# midicontrol_v4.net
KiCad netlist of a schematic drawn in EAGLE
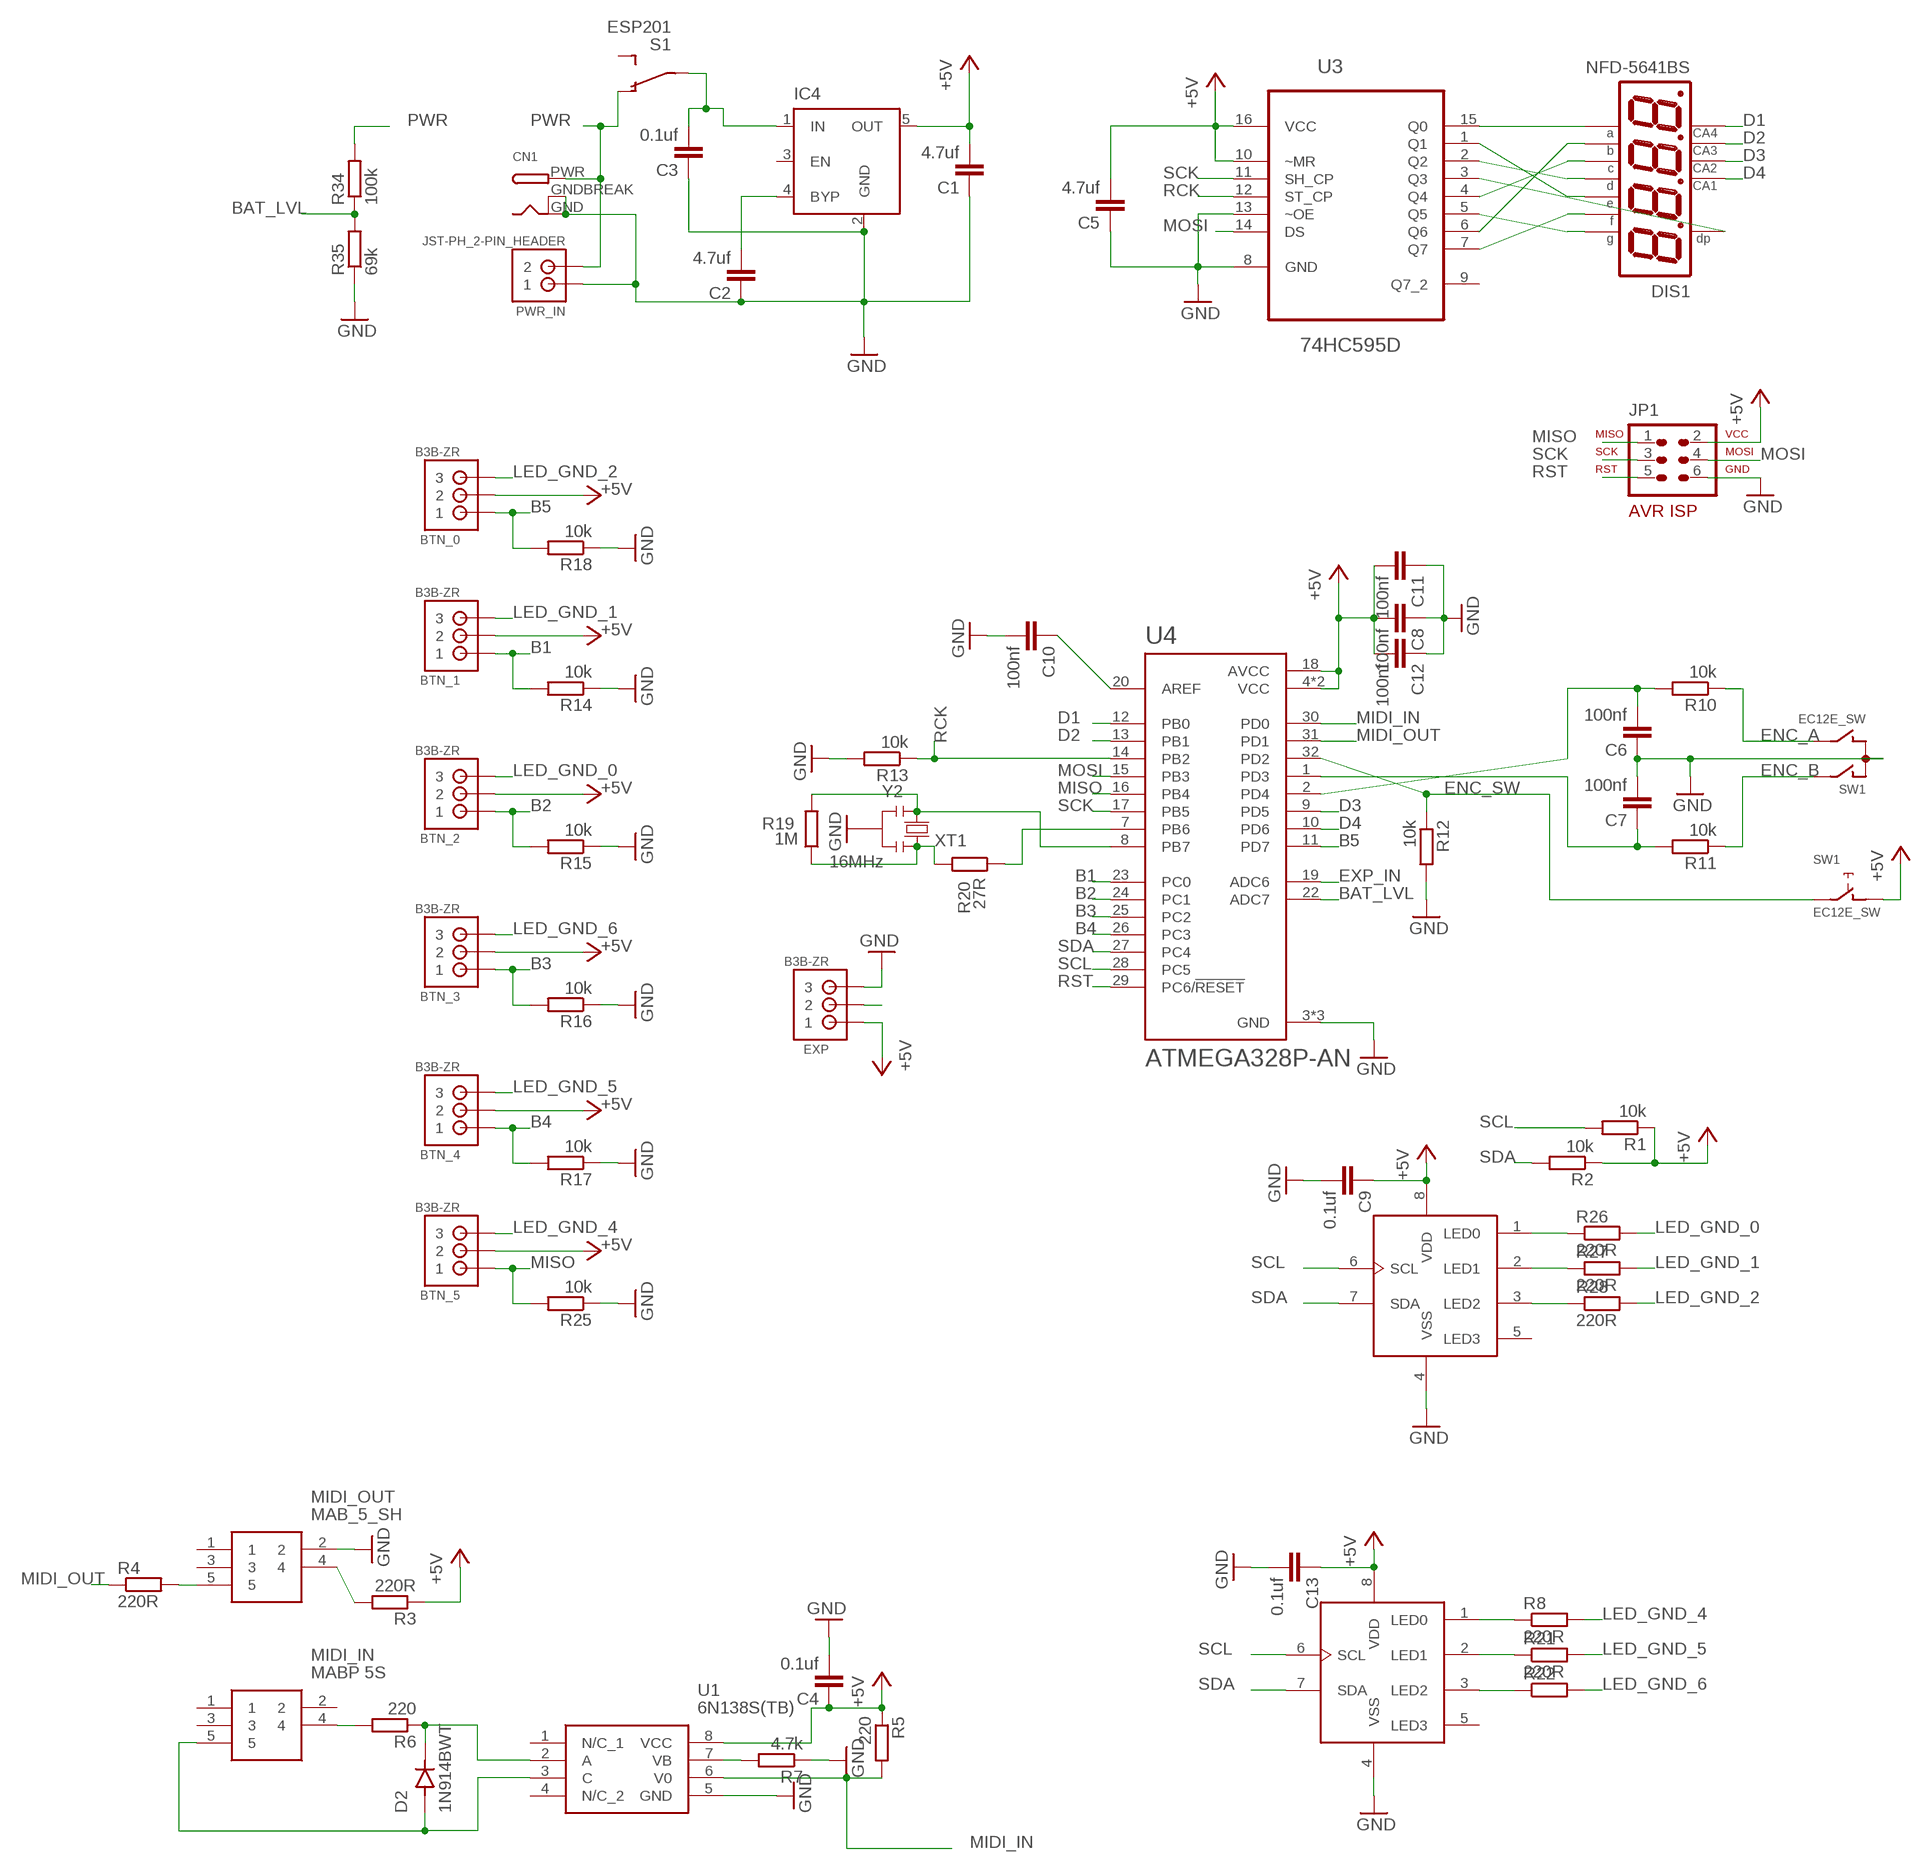
[diagram p0: schematic, sheet 1]

(export (version "E")
  (design (tool "Eeschema 10.0.6"))
  (components
    (comp (ref "BTN_0")
      (value "B3B-ZR")
      (footprint "eagle-import:B3B-ZR")
      (libsource (lib "eagle-import") (part "B3B-ZR"))
    )
    (comp (ref "BTN_1")
      (value "B3B-ZR")
      (footprint "eagle-import:B3B-ZR")
      (libsource (lib "eagle-import") (part "B3B-ZR"))
    )
    (comp (ref "BTN_2")
      (value "B3B-ZR")
      (footprint "eagle-import:B3B-ZR")
      (libsource (lib "eagle-import") (part "B3B-ZR"))
    )
    (comp (ref "BTN_3")
      (value "B3B-ZR")
      (footprint "eagle-import:B3B-ZR")
      (libsource (lib "eagle-import") (part "B3B-ZR"))
    )
    (comp (ref "BTN_4")
      (value "B3B-ZR")
      (footprint "eagle-import:B3B-ZR")
      (libsource (lib "eagle-import") (part "B3B-ZR"))
    )
    (comp (ref "BTN_5")
      (value "B3B-ZR")
      (footprint "eagle-import:B3B-ZR")
      (libsource (lib "eagle-import") (part "B3B-ZR"))
    )
    (comp (ref "C1")
      (value "4.7uf")
      (footprint "eagle-import:C1206")
      (libsource (lib "eagle-import") (part "C-EUC1206"))
    )
    (comp (ref "C2")
      (value "4.7uf")
      (footprint "eagle-import:C1206")
      (libsource (lib "eagle-import") (part "C-EUC1206"))
    )
    (comp (ref "C3")
      (value "0.1uf")
      (footprint "eagle-import:C1206")
      (libsource (lib "eagle-import") (part "C-EUC1206"))
    )
    (comp (ref "C4")
      (value "0.1uf")
      (footprint "eagle-import:C0603")
      (libsource (lib "eagle-import") (part "C-EUC0603"))
    )
    (comp (ref "C5")
      (value "4.7uf")
      (footprint "eagle-import:C0603")
      (libsource (lib "eagle-import") (part "C-EUC0603"))
    )
    (comp (ref "C6")
      (value "100nf")
      (footprint "eagle-import:C0603")
      (libsource (lib "eagle-import") (part "C-EUC0603"))
    )
    (comp (ref "C7")
      (value "100nf")
      (footprint "eagle-import:C0603")
      (libsource (lib "eagle-import") (part "C-EUC0603"))
    )
    (comp (ref "C8")
      (value "100nf")
      (footprint "eagle-import:C1206")
      (libsource (lib "eagle-import") (part "C-EUC1206"))
    )
    (comp (ref "C9")
      (value "0.1uf")
      (footprint "eagle-import:C0603")
      (libsource (lib "eagle-import") (part "C-EUC0603"))
    )
    (comp (ref "C10")
      (value "100nf")
      (footprint "eagle-import:C0603")
      (libsource (lib "eagle-import") (part "C-EUC0603"))
    )
    (comp (ref "C11")
      (value "100nf")
      (footprint "eagle-import:C0603")
      (libsource (lib "eagle-import") (part "C-EUC0603"))
    )
    (comp (ref "C12")
      (value "100nf")
      (footprint "eagle-import:C0603")
      (libsource (lib "eagle-import") (part "C-EUC0603"))
    )
    (comp (ref "C13")
      (value "0.1uf")
      (footprint "eagle-import:C0603")
      (libsource (lib "eagle-import") (part "C-EUC0603"))
    )
    (comp (ref "CN1")
      (value "DCBARRELPTH")
      (footprint "eagle-import:DCJACK_2MM_PTH")
      (libsource (lib "eagle-import") (part "DCBARRELPTH"))
    )
    (comp (ref "D2")
      (value "1N914BWT")
      (footprint "eagle-import:SODFL1608X70N")
      (fields (field (name "MF") "ON Semiconductor"))
      (libsource (lib "eagle-import") (part "1N914BWT"))
    )
    (comp (ref "DIS1")
      (value "NFD-5641BS")
      (footprint "eagle-import:NFD-5641")
      (libsource (lib "eagle-import") (part "NFD-5641BS"))
    )
    (comp (ref "EXP")
      (value "B3B-ZR")
      (footprint "eagle-import:B3B-ZR")
      (libsource (lib "eagle-import") (part "B3B-ZR"))
    )
    (comp (ref "IC4")
      (value "MIC5219XX")
      (footprint "eagle-import:SOT23-5")
      (libsource (lib "eagle-import") (part "MIC5219XX"))
    )
    (comp (ref "JP1")
      (value "AVR-ISP-6HORZ")
      (footprint "eagle-import:AVR-ISP-6R")
      (libsource (lib "eagle-import") (part "AVR-ISP-6HORZ"))
    )
    (comp (ref "MIDI_IN")
      (value "MABP 5S")
      (footprint "eagle-import:MAB-5-SH")
      (fields (field (name "MANUFACTURER_PART_NUMBER") "MAB 5 SH"))
      (libsource (lib "eagle-import") (part "MAB_5_SH"))
    )
    (comp (ref "MIDI_OUT")
      (value "MAB_5_SH")
      (footprint "eagle-import:MAB-5-SH")
      (fields (field (name "MANUFACTURER_PART_NUMBER") "MAB 5 SH"))
      (libsource (lib "eagle-import") (part "MAB_5_SH"))
    )
    (comp (ref "PCA1")
      (value "PCA9533")
      (footprint "eagle-import:SOIC8")
      (libsource (lib "eagle-import") (part "PCA9533"))
    )
    (comp (ref "PCA9533")
      (value "PCA9533")
      (footprint "eagle-import:SOIC8")
      (libsource (lib "eagle-import") (part "PCA9533"))
    )
    (comp (ref "PWR_IN")
      (value "JST-PH_2-PIN_HEADER")
      (footprint "eagle-import:JST_B2B-PH_HEADER")
      (libsource (lib "eagle-import") (part "JST-PH_2-PIN_HEADER"))
    )
    (comp (ref "R1")
      (value "10k")
      (footprint "eagle-import:R0603")
      (libsource (lib "eagle-import") (part "rcl_334_R-EU_R0603"))
    )
    (comp (ref "R2")
      (value "10k")
      (footprint "eagle-import:R0603")
      (libsource (lib "eagle-import") (part "rcl_334_R-EU_R0603"))
    )
    (comp (ref "R3")
      (value "220R")
      (footprint "eagle-import:R0603")
      (libsource (lib "eagle-import") (part "rcl_334_R-EU_R0603"))
    )
    (comp (ref "R4")
      (value "220R")
      (footprint "eagle-import:R0603")
      (libsource (lib "eagle-import") (part "rcl_334_R-EU_R0603"))
    )
    (comp (ref "R5")
      (value "220")
      (footprint "eagle-import:R0603")
      (libsource (lib "eagle-import") (part "rcl_334_R-EU_R0603"))
    )
    (comp (ref "R6")
      (value "220")
      (footprint "eagle-import:R0603")
      (libsource (lib "eagle-import") (part "rcl_334_R-EU_R0603"))
    )
    (comp (ref "R7")
      (value "4.7k")
      (footprint "eagle-import:R0603")
      (libsource (lib "eagle-import") (part "rcl_334_R-EU_R0603"))
    )
    (comp (ref "R8")
      (value "220R")
      (footprint "eagle-import:R0603")
      (libsource (lib "eagle-import") (part "rcl_334_R-EU_R0603"))
    )
    (comp (ref "R10")
      (value "10k")
      (footprint "eagle-import:R0603")
      (libsource (lib "eagle-import") (part "rcl_334_R-EU_R0603"))
    )
    (comp (ref "R11")
      (value "10k")
      (footprint "eagle-import:R0603")
      (libsource (lib "eagle-import") (part "rcl_334_R-EU_R0603"))
    )
    (comp (ref "R12")
      (value "10k")
      (footprint "eagle-import:R0603")
      (libsource (lib "eagle-import") (part "rcl_334_R-EU_R0603"))
    )
    (comp (ref "R13")
      (value "10k")
      (footprint "eagle-import:R0603")
      (libsource (lib "eagle-import") (part "rcl_334_R-EU_R0603"))
    )
    (comp (ref "R14")
      (value "10k")
      (footprint "eagle-import:R0603")
      (libsource (lib "eagle-import") (part "rcl_334_R-EU_R0603"))
    )
    (comp (ref "R15")
      (value "10k")
      (footprint "eagle-import:R0603")
      (libsource (lib "eagle-import") (part "rcl_334_R-EU_R0603"))
    )
    (comp (ref "R16")
      (value "10k")
      (footprint "eagle-import:R0603")
      (libsource (lib "eagle-import") (part "rcl_334_R-EU_R0603"))
    )
    (comp (ref "R17")
      (value "10k")
      (footprint "eagle-import:R0603")
      (libsource (lib "eagle-import") (part "rcl_334_R-EU_R0603"))
    )
    (comp (ref "R18")
      (value "10k")
      (footprint "eagle-import:R0603")
      (libsource (lib "eagle-import") (part "rcl_334_R-EU_R0603"))
    )
    (comp (ref "R19")
      (value "1M")
      (footprint "eagle-import:R0603-ROUND")
      (libsource (lib "eagle-import") (part "R-EU_R0603"))
    )
    (comp (ref "R20")
      (value "27R")
      (footprint "eagle-import:R0603-ROUND")
      (libsource (lib "eagle-import") (part "R-EU_R0603"))
    )
    (comp (ref "R21")
      (value "220R")
      (footprint "eagle-import:R0603")
      (libsource (lib "eagle-import") (part "rcl_334_R-EU_R0603"))
    )
    (comp (ref "R22")
      (value "220R")
      (footprint "eagle-import:R0603")
      (libsource (lib "eagle-import") (part "rcl_334_R-EU_R0603"))
    )
    (comp (ref "R25")
      (value "10k")
      (footprint "eagle-import:R0603")
      (libsource (lib "eagle-import") (part "rcl_334_R-EU_R0603"))
    )
    (comp (ref "R26")
      (value "220R")
      (footprint "eagle-import:R0603")
      (libsource (lib "eagle-import") (part "rcl_334_R-EU_R0603"))
    )
    (comp (ref "R27")
      (value "220R")
      (footprint "eagle-import:R0603")
      (libsource (lib "eagle-import") (part "rcl_334_R-EU_R0603"))
    )
    (comp (ref "R28")
      (value "220R")
      (footprint "eagle-import:R0603")
      (libsource (lib "eagle-import") (part "rcl_334_R-EU_R0603"))
    )
    (comp (ref "R34")
      (value "100k")
      (footprint "eagle-import:R0603")
      (libsource (lib "eagle-import") (part "rcl_334_R-EU_R0603"))
    )
    (comp (ref "R35")
      (value "69k")
      (footprint "eagle-import:R0603")
      (libsource (lib "eagle-import") (part "rcl_334_R-EU_R0603"))
    )
    (comp (ref "S1")
      (value "ESP201")
      (footprint "eagle-import:ESP201")
      (libsource (lib "eagle-import") (part "ESP201"))
    )
    (comp (ref "SW1")
      (value "EC12E_SW")
      (footprint "eagle-import:ALPS_EC12E_SW")
      (fields (field (name "MPN") "EC12E2424407"))
      (libsource (lib "eagle-import") (part "EC12E_SW"))
    )
    (comp (ref "U1")
      (value "6N138S(TB)")
      (footprint "eagle-import:SOP254P1030X460-8N")
      (fields (field (name "MOUSER_PART_NUMBER") "638-6N138STB"))
      (libsource (lib "eagle-import") (part "6N138S(TB)"))
    )
    (comp (ref "U3")
      (value "74HC595D")
      (footprint "eagle-import:SOIC127P600X175-16N")
      (fields (field (name "MF") "Toshiba Semiconductor"))
      (libsource (lib "eagle-import") (part "74HC595D"))
    )
    (comp (ref "U4")
      (value "ATMEGA328P-AN")
      (footprint "eagle-import:QFP80P900X900X120-32N")
      (fields (field (name "MF") "Microchip"))
      (libsource (lib "eagle-import") (part "ATMEGA328P-AN"))
    )
    (comp (ref "Y2")
      (value "16MHz")
      (footprint "eagle-import:RESONATOR")
      (libsource (lib "eagle-import") (part "RESONATORMU"))
    )
  )
  (nets
    (net (code "1") (name "+5V") (class "Default")
      (node (ref "BTN_0") (pin "2") (pinfunction "2_2") (pintype "bidirectional"))
      (node (ref "BTN_1") (pin "2") (pinfunction "2_2") (pintype "bidirectional"))
      (node (ref "BTN_2") (pin "2") (pinfunction "2_2") (pintype "bidirectional"))
      (node (ref "BTN_3") (pin "2") (pinfunction "2_2") (pintype "bidirectional"))
      (node (ref "BTN_4") (pin "2") (pinfunction "2_2") (pintype "bidirectional"))
      (node (ref "BTN_5") (pin "2") (pinfunction "2_2") (pintype "bidirectional"))
      (node (ref "C1") (pin "2") (pinfunction "2_2") (pintype "passive"))
      (node (ref "C11") (pin "2") (pinfunction "2_2") (pintype "passive"))
      (node (ref "C12") (pin "2") (pinfunction "2_2") (pintype "passive"))
      (node (ref "C13") (pin "1") (pinfunction "1_1") (pintype "passive"))
      (node (ref "C4") (pin "1") (pinfunction "1_1") (pintype "passive"))
      (node (ref "C5") (pin "2") (pinfunction "2_2") (pintype "passive"))
      (node (ref "C8") (pin "2") (pinfunction "2_2") (pintype "passive"))
      (node (ref "C9") (pin "1") (pinfunction "1_1") (pintype "passive"))
      (node (ref "EXP") (pin "1") (pinfunction "1_1") (pintype "bidirectional"))
      (node (ref "IC4") (pin "5") (pinfunction "OUT_5") (pintype "output"))
      (node (ref "JP1") (pin "2") (pinfunction "2_2") (pintype "passive"))
      (node (ref "PCA1") (pin "8") (pinfunction "VDD_8") (pintype "power_in"))
      (node (ref "PCA9533") (pin "8") (pinfunction "VDD_8") (pintype "power_in"))
      (node (ref "R1") (pin "1") (pinfunction "1_1") (pintype "passive"))
      (node (ref "R2") (pin "1") (pinfunction "1_1") (pintype "passive"))
      (node (ref "R3") (pin "1") (pinfunction "1_1") (pintype "passive"))
      (node (ref "R5") (pin "1") (pinfunction "1_1") (pintype "passive"))
      (node (ref "SW1") (pin "D") (pinfunction "1_D") (pintype "passive"))
      (node (ref "U1") (pin "8") (pinfunction "VCC_8") (pintype "power_in"))
      (node (ref "U3") (pin "10") (pinfunction "~{MR}_10") (pintype "passive"))
      (node (ref "U3") (pin "16") (pinfunction "VCC_16") (pintype "power_in"))
      (node (ref "U4") (pin "18") (pinfunction "AVCC_18") (pintype "power_in"))
      (node (ref "U4") (pin "4") (pinfunction "VCC_4") (pintype "power_in"))
      (node (ref "U4") (pin "6") (pinfunction "VCC_6") (pintype "power_in"))
    )
    (net (code "2") (name "/B1") (class "Default")
      (node (ref "BTN_1") (pin "1") (pinfunction "1_1") (pintype "bidirectional"))
      (node (ref "R14") (pin "2") (pinfunction "2_2") (pintype "passive"))
      (node (ref "U4") (pin "23") (pinfunction "PC0_23") (pintype "bidirectional"))
    )
    (net (code "3") (name "/B2") (class "Default")
      (node (ref "BTN_2") (pin "1") (pinfunction "1_1") (pintype "bidirectional"))
      (node (ref "R15") (pin "2") (pinfunction "2_2") (pintype "passive"))
      (node (ref "U4") (pin "24") (pinfunction "PC1_24") (pintype "bidirectional"))
    )
    (net (code "4") (name "/B3") (class "Default")
      (node (ref "BTN_3") (pin "1") (pinfunction "1_1") (pintype "bidirectional"))
      (node (ref "R16") (pin "2") (pinfunction "2_2") (pintype "passive"))
      (node (ref "U4") (pin "25") (pinfunction "PC2_25") (pintype "bidirectional"))
    )
    (net (code "5") (name "/B4") (class "Default")
      (node (ref "BTN_4") (pin "1") (pinfunction "1_1") (pintype "bidirectional"))
      (node (ref "R17") (pin "2") (pinfunction "2_2") (pintype "passive"))
      (node (ref "U4") (pin "26") (pinfunction "PC3_26") (pintype "bidirectional"))
    )
    (net (code "6") (name "/B5") (class "Default")
      (node (ref "BTN_0") (pin "1") (pinfunction "1_1") (pintype "bidirectional"))
      (node (ref "R18") (pin "2") (pinfunction "2_2") (pintype "passive"))
      (node (ref "U4") (pin "11") (pinfunction "PD7_11") (pintype "bidirectional"))
    )
    (net (code "7") (name "/BAT_LVL") (class "Default")
      (node (ref "R34") (pin "1") (pinfunction "1_1") (pintype "passive"))
      (node (ref "R35") (pin "2") (pinfunction "2_2") (pintype "passive"))
      (node (ref "U4") (pin "22") (pinfunction "ADC7_22") (pintype "bidirectional"))
    )
    (net (code "8") (name "/D1") (class "Default")
      (node (ref "DIS1") (pin "P$6") (pinfunction "P$6_P$6") (pintype "bidirectional"))
      (node (ref "U4") (pin "12") (pinfunction "PB0_12") (pintype "bidirectional"))
    )
    (net (code "9") (name "/D2") (class "Default")
      (node (ref "DIS1") (pin "P$8") (pinfunction "P$8_P$8") (pintype "bidirectional"))
      (node (ref "U4") (pin "13") (pinfunction "PB1_13") (pintype "bidirectional"))
    )
    (net (code "10") (name "/D3") (class "Default")
      (node (ref "DIS1") (pin "P$9") (pinfunction "P$9_P$9") (pintype "bidirectional"))
      (node (ref "U4") (pin "9") (pinfunction "PD5_9") (pintype "bidirectional"))
    )
    (net (code "11") (name "/D4") (class "Default")
      (node (ref "DIS1") (pin "P$12") (pinfunction "P$12_P$12") (pintype "bidirectional"))
      (node (ref "U4") (pin "10") (pinfunction "PD6_10") (pintype "bidirectional"))
    )
    (net (code "12") (name "/ENC_A") (class "Default")
      (node (ref "R10") (pin "1") (pinfunction "1_1") (pintype "passive"))
      (node (ref "SW1") (pin "B") (pinfunction "B_B") (pintype "passive"))
    )
    (net (code "13") (name "/ENC_B") (class "Default")
      (node (ref "R11") (pin "1") (pinfunction "1_1") (pintype "passive"))
      (node (ref "SW1") (pin "A") (pinfunction "A_A") (pintype "passive"))
    )
    (net (code "14") (name "/ENC_SW") (class "Default")
      (node (ref "R12") (pin "1") (pinfunction "1_1") (pintype "passive"))
      (node (ref "SW1") (pin "E") (pinfunction "2_E") (pintype "passive"))
      (node (ref "U4") (pin "32") (pinfunction "PD2_32") (pintype "bidirectional"))
    )
    (net (code "15") (name "/EXP_IN") (class "Default")
      (node (ref "EXP") (pin "2") (pinfunction "2_2") (pintype "bidirectional"))
      (node (ref "U4") (pin "19") (pinfunction "ADC6_19") (pintype "bidirectional"))
    )
    (net (code "16") (name "/LED_GND_0") (class "Default")
      (node (ref "BTN_2") (pin "3") (pinfunction "3_3") (pintype "bidirectional"))
      (node (ref "R26") (pin "2") (pinfunction "2_2") (pintype "passive"))
    )
    (net (code "17") (name "/LED_GND_1") (class "Default")
      (node (ref "BTN_1") (pin "3") (pinfunction "3_3") (pintype "bidirectional"))
      (node (ref "R27") (pin "2") (pinfunction "2_2") (pintype "passive"))
    )
    (net (code "18") (name "/LED_GND_2") (class "Default")
      (node (ref "BTN_0") (pin "3") (pinfunction "3_3") (pintype "bidirectional"))
      (node (ref "R28") (pin "2") (pinfunction "2_2") (pintype "passive"))
    )
    (net (code "19") (name "/LED_GND_4") (class "Default")
      (node (ref "BTN_5") (pin "3") (pinfunction "3_3") (pintype "bidirectional"))
      (node (ref "R8") (pin "2") (pinfunction "2_2") (pintype "passive"))
    )
    (net (code "20") (name "/LED_GND_5") (class "Default")
      (node (ref "BTN_4") (pin "3") (pinfunction "3_3") (pintype "bidirectional"))
      (node (ref "R21") (pin "2") (pinfunction "2_2") (pintype "passive"))
    )
    (net (code "21") (name "/LED_GND_6") (class "Default")
      (node (ref "BTN_3") (pin "3") (pinfunction "3_3") (pintype "bidirectional"))
      (node (ref "R22") (pin "2") (pinfunction "2_2") (pintype "passive"))
    )
    (net (code "22") (name "/MIDI_IN") (class "Default")
      (node (ref "R5") (pin "2") (pinfunction "2_2") (pintype "passive"))
      (node (ref "U1") (pin "6") (pinfunction "V0_6") (pintype "bidirectional"))
      (node (ref "U4") (pin "30") (pinfunction "PD0_30") (pintype "bidirectional"))
    )
    (net (code "23") (name "/MIDI_OUT") (class "Default")
      (node (ref "R4") (pin "1") (pinfunction "1_1") (pintype "passive"))
      (node (ref "U4") (pin "31") (pinfunction "PD1_31") (pintype "bidirectional"))
    )
    (net (code "24") (name "/MISO") (class "Default")
      (node (ref "BTN_5") (pin "1") (pinfunction "1_1") (pintype "bidirectional"))
      (node (ref "JP1") (pin "1") (pinfunction "1_1") (pintype "passive"))
      (node (ref "R25") (pin "2") (pinfunction "2_2") (pintype "passive"))
      (node (ref "U4") (pin "16") (pinfunction "PB4_16") (pintype "bidirectional"))
    )
    (net (code "25") (name "/MOSI") (class "Default")
      (node (ref "JP1") (pin "4") (pinfunction "4_4") (pintype "passive"))
      (node (ref "U3") (pin "14") (pinfunction "DS_14") (pintype "input"))
      (node (ref "U4") (pin "15") (pinfunction "PB3_15") (pintype "bidirectional"))
    )
    (net (code "26") (name "/PWR") (class "Default")
      (node (ref "CN1") (pin "PWR") (pinfunction "PWR_PWR") (pintype "power_in"))
      (node (ref "PWR_IN") (pin "P2") (pinfunction "2_P2") (pintype "bidirectional"))
      (node (ref "R34") (pin "2") (pinfunction "2_2") (pintype "passive"))
      (node (ref "S1") (pin "P$3") (pinfunction "O_P$3") (pintype "passive"))
    )
    (net (code "27") (name "/RCK") (class "Default")
      (node (ref "R13") (pin "1") (pinfunction "1_1") (pintype "passive"))
      (node (ref "U3") (pin "12") (pinfunction "ST_CP_12") (pintype "passive"))
      (node (ref "U4") (pin "14") (pinfunction "PB2_14") (pintype "bidirectional"))
    )
    (net (code "28") (name "/RST") (class "Default")
      (node (ref "JP1") (pin "5") (pinfunction "5_5") (pintype "passive"))
      (node (ref "U4") (pin "29") (pinfunction "PC6/~{RESET}_29") (pintype "bidirectional"))
    )
    (net (code "29") (name "/SCK") (class "Default")
      (node (ref "JP1") (pin "3") (pinfunction "3_3") (pintype "passive"))
      (node (ref "U3") (pin "11") (pinfunction "SH_CP_11") (pintype "passive"))
      (node (ref "U4") (pin "17") (pinfunction "PB5_17") (pintype "bidirectional"))
    )
    (net (code "30") (name "/SCL") (class "Default")
      (node (ref "PCA1") (pin "6") (pinfunction "SCL_6") (pintype "input"))
      (node (ref "PCA9533") (pin "6") (pinfunction "SCL_6") (pintype "input"))
      (node (ref "R1") (pin "2") (pinfunction "2_2") (pintype "passive"))
      (node (ref "U4") (pin "28") (pinfunction "PC5_28") (pintype "bidirectional"))
    )
    (net (code "31") (name "/SDA") (class "Default")
      (node (ref "PCA1") (pin "7") (pinfunction "SDA_7") (pintype "bidirectional"))
      (node (ref "PCA9533") (pin "7") (pinfunction "SDA_7") (pintype "bidirectional"))
      (node (ref "R2") (pin "2") (pinfunction "2_2") (pintype "passive"))
      (node (ref "U4") (pin "27") (pinfunction "PC4_27") (pintype "bidirectional"))
    )
    (net (code "32") (name "/XT1") (class "Default")
      (node (ref "R19") (pin "1") (pinfunction "1_1") (pintype "passive"))
      (node (ref "R20") (pin "2") (pinfunction "2_2") (pintype "passive"))
      (node (ref "Y2") (pin "3") (pinfunction "3_3") (pintype "passive"))
    )
    (net (code "33") (name "GND") (class "Default")
      (node (ref "C1") (pin "1") (pinfunction "1_1") (pintype "passive"))
      (node (ref "C10") (pin "2") (pinfunction "2_2") (pintype "passive"))
      (node (ref "C11") (pin "1") (pinfunction "1_1") (pintype "passive"))
      (node (ref "C12") (pin "1") (pinfunction "1_1") (pintype "passive"))
      (node (ref "C13") (pin "2") (pinfunction "2_2") (pintype "passive"))
      (node (ref "C2") (pin "1") (pinfunction "1_1") (pintype "passive"))
      (node (ref "C3") (pin "1") (pinfunction "1_1") (pintype "passive"))
      (node (ref "C4") (pin "2") (pinfunction "2_2") (pintype "passive"))
      (node (ref "C5") (pin "1") (pinfunction "1_1") (pintype "passive"))
      (node (ref "C6") (pin "1") (pinfunction "1_1") (pintype "passive"))
      (node (ref "C7") (pin "2") (pinfunction "2_2") (pintype "passive"))
      (node (ref "C8") (pin "1") (pinfunction "1_1") (pintype "passive"))
      (node (ref "C9") (pin "2") (pinfunction "2_2") (pintype "passive"))
      (node (ref "CN1") (pin "GND") (pinfunction "GND_GND") (pintype "power_in"))
      (node (ref "CN1") (pin "GNDBREAK") (pinfunction "GNDBREAK_GNDBREAK") (pintype "power_in"))
      (node (ref "EXP") (pin "3") (pinfunction "3_3") (pintype "bidirectional"))
      (node (ref "IC4") (pin "2") (pinfunction "GND_2") (pintype "power_in"))
      (node (ref "JP1") (pin "6") (pinfunction "6_6") (pintype "passive"))
      (node (ref "MIDI_OUT") (pin "2") (pinfunction "2_2") (pintype "bidirectional"))
      (node (ref "PCA1") (pin "4") (pinfunction "VSS_4") (pintype "power_in"))
      (node (ref "PCA9533") (pin "4") (pinfunction "VSS_4") (pintype "power_in"))
      (node (ref "PWR_IN") (pin "P1") (pinfunction "1_P1") (pintype "bidirectional"))
      (node (ref "R12") (pin "2") (pinfunction "2_2") (pintype "passive"))
      (node (ref "R13") (pin "2") (pinfunction "2_2") (pintype "passive"))
      (node (ref "R14") (pin "1") (pinfunction "1_1") (pintype "passive"))
      (node (ref "R15") (pin "1") (pinfunction "1_1") (pintype "passive"))
      (node (ref "R16") (pin "1") (pinfunction "1_1") (pintype "passive"))
      (node (ref "R17") (pin "1") (pinfunction "1_1") (pintype "passive"))
      (node (ref "R18") (pin "1") (pinfunction "1_1") (pintype "passive"))
      (node (ref "R25") (pin "1") (pinfunction "1_1") (pintype "passive"))
      (node (ref "R35") (pin "1") (pinfunction "1_1") (pintype "passive"))
      (node (ref "R7") (pin "1") (pinfunction "1_1") (pintype "passive"))
      (node (ref "SW1") (pin "C") (pinfunction "C_C") (pintype "passive"))
      (node (ref "U1") (pin "5") (pinfunction "GND_5") (pintype "power_in"))
      (node (ref "U3") (pin "13") (pinfunction "~{OE}_13") (pintype "input"))
      (node (ref "U3") (pin "8") (pinfunction "GND_8") (pintype "passive"))
      (node (ref "U4") (pin "21") (pinfunction "GND_21") (pintype "power_in"))
      (node (ref "U4") (pin "3") (pinfunction "GND_3") (pintype "power_in"))
      (node (ref "U4") (pin "5") (pinfunction "GND_5") (pintype "power_in"))
      (node (ref "Y2") (pin "2") (pinfunction "2_2") (pintype "passive"))
    )
    (net (code "34") (name "Net-(D2-K)") (class "Default")
      (node (ref "D2") (pin "C") (pinfunction "K_C") (pintype "passive"))
      (node (ref "R6") (pin "1") (pinfunction "1_1") (pintype "passive"))
      (node (ref "U1") (pin "2") (pinfunction "A_2") (pintype "bidirectional"))
    )
    (net (code "35") (name "Net-(IC4-BYP)") (class "Default")
      (node (ref "C2") (pin "2") (pinfunction "2_2") (pintype "passive"))
      (node (ref "IC4") (pin "4") (pinfunction "BYP_4") (pintype "passive"))
    )
    (net (code "36") (name "Net-(IC4-IN)") (class "Default")
      (node (ref "C3") (pin "2") (pinfunction "2_2") (pintype "passive"))
      (node (ref "IC4") (pin "1") (pinfunction "IN_1") (pintype "input"))
      (node (ref "S1") (pin "P$1") (pinfunction "P_P$1") (pintype "passive"))
    )
    (net (code "37") (name "Net-(MIDI_IN-Pad4)") (class "Default")
      (node (ref "MIDI_IN") (pin "4") (pinfunction "4_4") (pintype "bidirectional"))
      (node (ref "R6") (pin "2") (pinfunction "2_2") (pintype "passive"))
    )
    (net (code "38") (name "Net-(MIDI_OUT-Pad4)") (class "Default")
      (node (ref "MIDI_OUT") (pin "4") (pinfunction "4_4") (pintype "bidirectional"))
      (node (ref "R3") (pin "2") (pinfunction "2_2") (pintype "passive"))
    )
    (net (code "39") (name "Net-(MIDI_OUT-Pad5)") (class "Default")
      (node (ref "MIDI_OUT") (pin "5") (pinfunction "5_5") (pintype "bidirectional"))
      (node (ref "R4") (pin "2") (pinfunction "2_2") (pintype "passive"))
    )
    (net (code "40") (name "Net-(PCA1-LED0)") (class "Default")
      (node (ref "PCA1") (pin "1") (pinfunction "LED0_1") (pintype "bidirectional"))
      (node (ref "R8") (pin "1") (pinfunction "1_1") (pintype "passive"))
    )
    (net (code "41") (name "Net-(PCA1-LED1)") (class "Default")
      (node (ref "PCA1") (pin "2") (pinfunction "LED1_2") (pintype "bidirectional"))
      (node (ref "R21") (pin "1") (pinfunction "1_1") (pintype "passive"))
    )
    (net (code "42") (name "Net-(PCA1-LED2)") (class "Default")
      (node (ref "PCA1") (pin "3") (pinfunction "LED2_3") (pintype "bidirectional"))
      (node (ref "R22") (pin "1") (pinfunction "1_1") (pintype "passive"))
    )
    (net (code "43") (name "Net-(PCA9533-LED0)") (class "Default")
      (node (ref "PCA9533") (pin "1") (pinfunction "LED0_1") (pintype "bidirectional"))
      (node (ref "R26") (pin "1") (pinfunction "1_1") (pintype "passive"))
    )
    (net (code "44") (name "Net-(PCA9533-LED1)") (class "Default")
      (node (ref "PCA9533") (pin "2") (pinfunction "LED1_2") (pintype "bidirectional"))
      (node (ref "R27") (pin "1") (pinfunction "1_1") (pintype "passive"))
    )
    (net (code "45") (name "Net-(PCA9533-LED2)") (class "Default")
      (node (ref "PCA9533") (pin "3") (pinfunction "LED2_3") (pintype "bidirectional"))
      (node (ref "R28") (pin "1") (pinfunction "1_1") (pintype "passive"))
    )
    (net (code "46") (name "Net-(U1-C)") (class "Default")
      (node (ref "D2") (pin "A") (pinfunction "A_A") (pintype "passive"))
      (node (ref "MIDI_IN") (pin "5") (pinfunction "5_5") (pintype "bidirectional"))
      (node (ref "U1") (pin "3") (pinfunction "C_3") (pintype "bidirectional"))
    )
    (net (code "47") (name "Net-(U1-VB)") (class "Default")
      (node (ref "R7") (pin "2") (pinfunction "2_2") (pintype "passive"))
      (node (ref "U1") (pin "7") (pinfunction "VB_7") (pintype "bidirectional"))
    )
    (net (code "48") (name "Net-(U3-Q0)") (class "Default")
      (node (ref "DIS1") (pin "P$11") (pinfunction "P$11_P$11") (pintype "bidirectional"))
      (node (ref "U3") (pin "15") (pinfunction "Q0_15") (pintype "output"))
    )
    (net (code "49") (name "Net-(U3-Q1)") (class "Default")
      (node (ref "DIS1") (pin "P$1") (pinfunction "P$1_P$1") (pintype "bidirectional"))
      (node (ref "U3") (pin "1") (pinfunction "Q1_1") (pintype "output"))
    )
    (net (code "50") (name "Net-(U3-Q2)") (class "Default")
      (node (ref "DIS1") (pin "P$2") (pinfunction "P$2_P$2") (pintype "bidirectional"))
      (node (ref "U3") (pin "2") (pinfunction "Q2_2") (pintype "output"))
    )
    (net (code "51") (name "Net-(U3-Q3)") (class "Default")
      (node (ref "DIS1") (pin "P$3") (pinfunction "P$3_P$3") (pintype "bidirectional"))
      (node (ref "U3") (pin "3") (pinfunction "Q3_3") (pintype "output"))
    )
    (net (code "52") (name "Net-(U3-Q4)") (class "Default")
      (node (ref "DIS1") (pin "P$4") (pinfunction "P$4_P$4") (pintype "bidirectional"))
      (node (ref "U3") (pin "4") (pinfunction "Q4_4") (pintype "output"))
    )
    (net (code "53") (name "Net-(U3-Q5)") (class "Default")
      (node (ref "DIS1") (pin "P$5") (pinfunction "P$5_P$5") (pintype "bidirectional"))
      (node (ref "U3") (pin "5") (pinfunction "Q5_5") (pintype "output"))
    )
    (net (code "54") (name "Net-(U3-Q6)") (class "Default")
      (node (ref "DIS1") (pin "P$7") (pinfunction "P$7_P$7") (pintype "bidirectional"))
      (node (ref "U3") (pin "6") (pinfunction "Q6_6") (pintype "output"))
    )
    (net (code "55") (name "Net-(U3-Q7)") (class "Default")
      (node (ref "DIS1") (pin "P$10") (pinfunction "P$10_P$10") (pintype "bidirectional"))
      (node (ref "U3") (pin "7") (pinfunction "Q7_7") (pintype "output"))
    )
    (net (code "56") (name "Net-(U4-AREF)") (class "Default")
      (node (ref "C10") (pin "1") (pinfunction "1_1") (pintype "passive"))
      (node (ref "U4") (pin "20") (pinfunction "AREF_20") (pintype "input"))
    )
    (net (code "57") (name "Net-(U4-PB6)") (class "Default")
      (node (ref "R20") (pin "1") (pinfunction "1_1") (pintype "passive"))
      (node (ref "U4") (pin "7") (pinfunction "PB6_7") (pintype "bidirectional"))
    )
    (net (code "58") (name "Net-(U4-PB7)") (class "Default")
      (node (ref "R19") (pin "2") (pinfunction "2_2") (pintype "passive"))
      (node (ref "U4") (pin "8") (pinfunction "PB7_8") (pintype "bidirectional"))
      (node (ref "Y2") (pin "1") (pinfunction "1_1") (pintype "passive"))
    )
    (net (code "59") (name "Net-(U4-PD3)") (class "Default")
      (node (ref "C7") (pin "1") (pinfunction "1_1") (pintype "passive"))
      (node (ref "R11") (pin "2") (pinfunction "2_2") (pintype "passive"))
      (node (ref "U4") (pin "1") (pinfunction "PD3_1") (pintype "bidirectional"))
    )
    (net (code "60") (name "Net-(U4-PD4)") (class "Default")
      (node (ref "C6") (pin "2") (pinfunction "2_2") (pintype "passive"))
      (node (ref "R10") (pin "2") (pinfunction "2_2") (pintype "passive"))
      (node (ref "U4") (pin "2") (pinfunction "PD4_2") (pintype "bidirectional"))
    )
    (net (code "61") (name "unconnected-(IC4-EN-Pad3)") (class "Default")
      (node (ref "IC4") (pin "3") (pinfunction "EN_3") (pintype "input"))
    )
    (net (code "62") (name "unconnected-(MIDI_IN-Pad1)") (class "Default")
      (node (ref "MIDI_IN") (pin "1") (pinfunction "1_1") (pintype "bidirectional"))
    )
    (net (code "63") (name "unconnected-(MIDI_IN-Pad2)") (class "Default")
      (node (ref "MIDI_IN") (pin "2") (pinfunction "2_2") (pintype "bidirectional"))
    )
    (net (code "64") (name "unconnected-(MIDI_IN-Pad3)") (class "Default")
      (node (ref "MIDI_IN") (pin "3") (pinfunction "3_3") (pintype "bidirectional"))
    )
    (net (code "65") (name "unconnected-(MIDI_OUT-Pad1)") (class "Default")
      (node (ref "MIDI_OUT") (pin "1") (pinfunction "1_1") (pintype "bidirectional"))
    )
    (net (code "66") (name "unconnected-(MIDI_OUT-Pad3)") (class "Default")
      (node (ref "MIDI_OUT") (pin "3") (pinfunction "3_3") (pintype "bidirectional"))
    )
    (net (code "67") (name "unconnected-(PCA1-LED3-Pad5)") (class "Default")
      (node (ref "PCA1") (pin "5") (pinfunction "LED3_5") (pintype "bidirectional"))
    )
    (net (code "68") (name "unconnected-(PCA9533-LED3-Pad5)") (class "Default")
      (node (ref "PCA9533") (pin "5") (pinfunction "LED3_5") (pintype "bidirectional"))
    )
    (net (code "69") (name "unconnected-(S1-S-PadP$2)") (class "Default")
      (node (ref "S1") (pin "P$2") (pinfunction "S_P$2") (pintype "passive"))
    )
    (net (code "70") (name "unconnected-(U1-N{slash}C_1-Pad1)") (class "Default")
      (node (ref "U1") (pin "1") (pinfunction "N/C_1_1") (pintype "bidirectional"))
    )
    (net (code "71") (name "unconnected-(U1-N{slash}C_2-Pad4)") (class "Default")
      (node (ref "U1") (pin "4") (pinfunction "N/C_2_4") (pintype "bidirectional"))
    )
    (net (code "72") (name "unconnected-(U3-Q7_2-Pad9)") (class "Default")
      (node (ref "U3") (pin "9") (pinfunction "Q7_2_9") (pintype "output"))
    )
  )
)
